# sweet_board_2020-08-14_14-36-53.net
KiCad netlist of a schematic drawn in EasyEDA
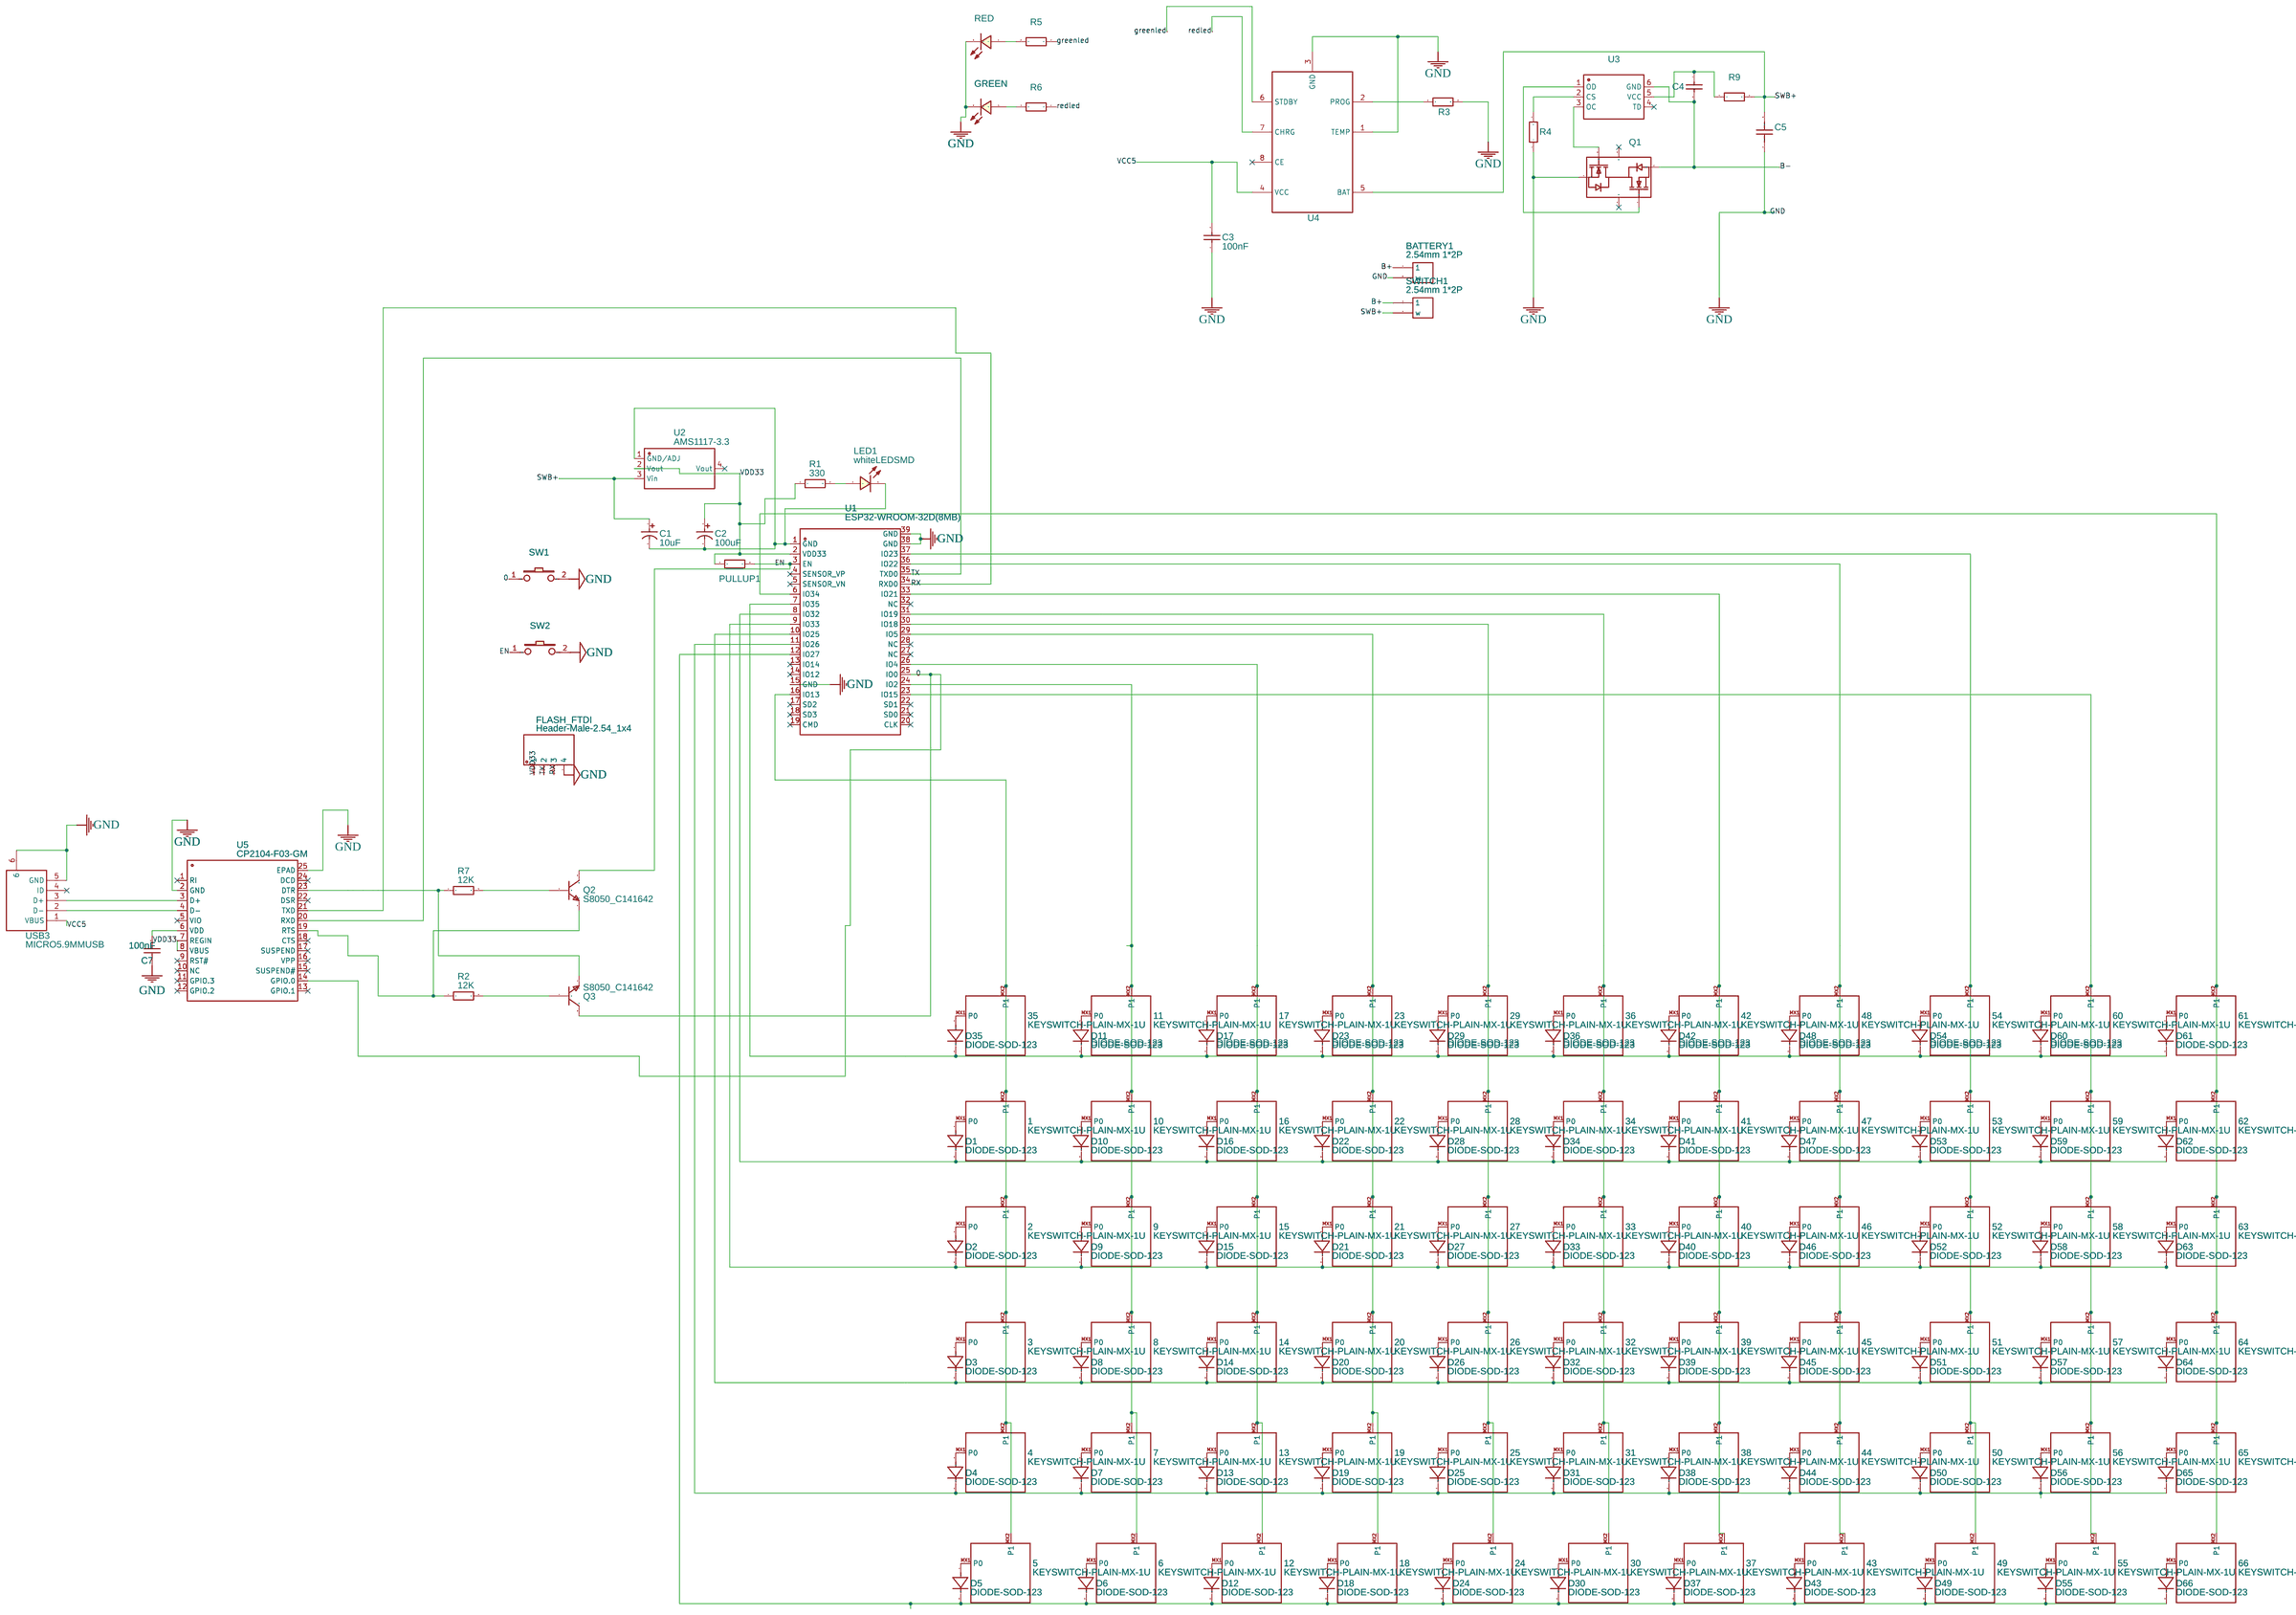
[diagram p0: Sheet_1]
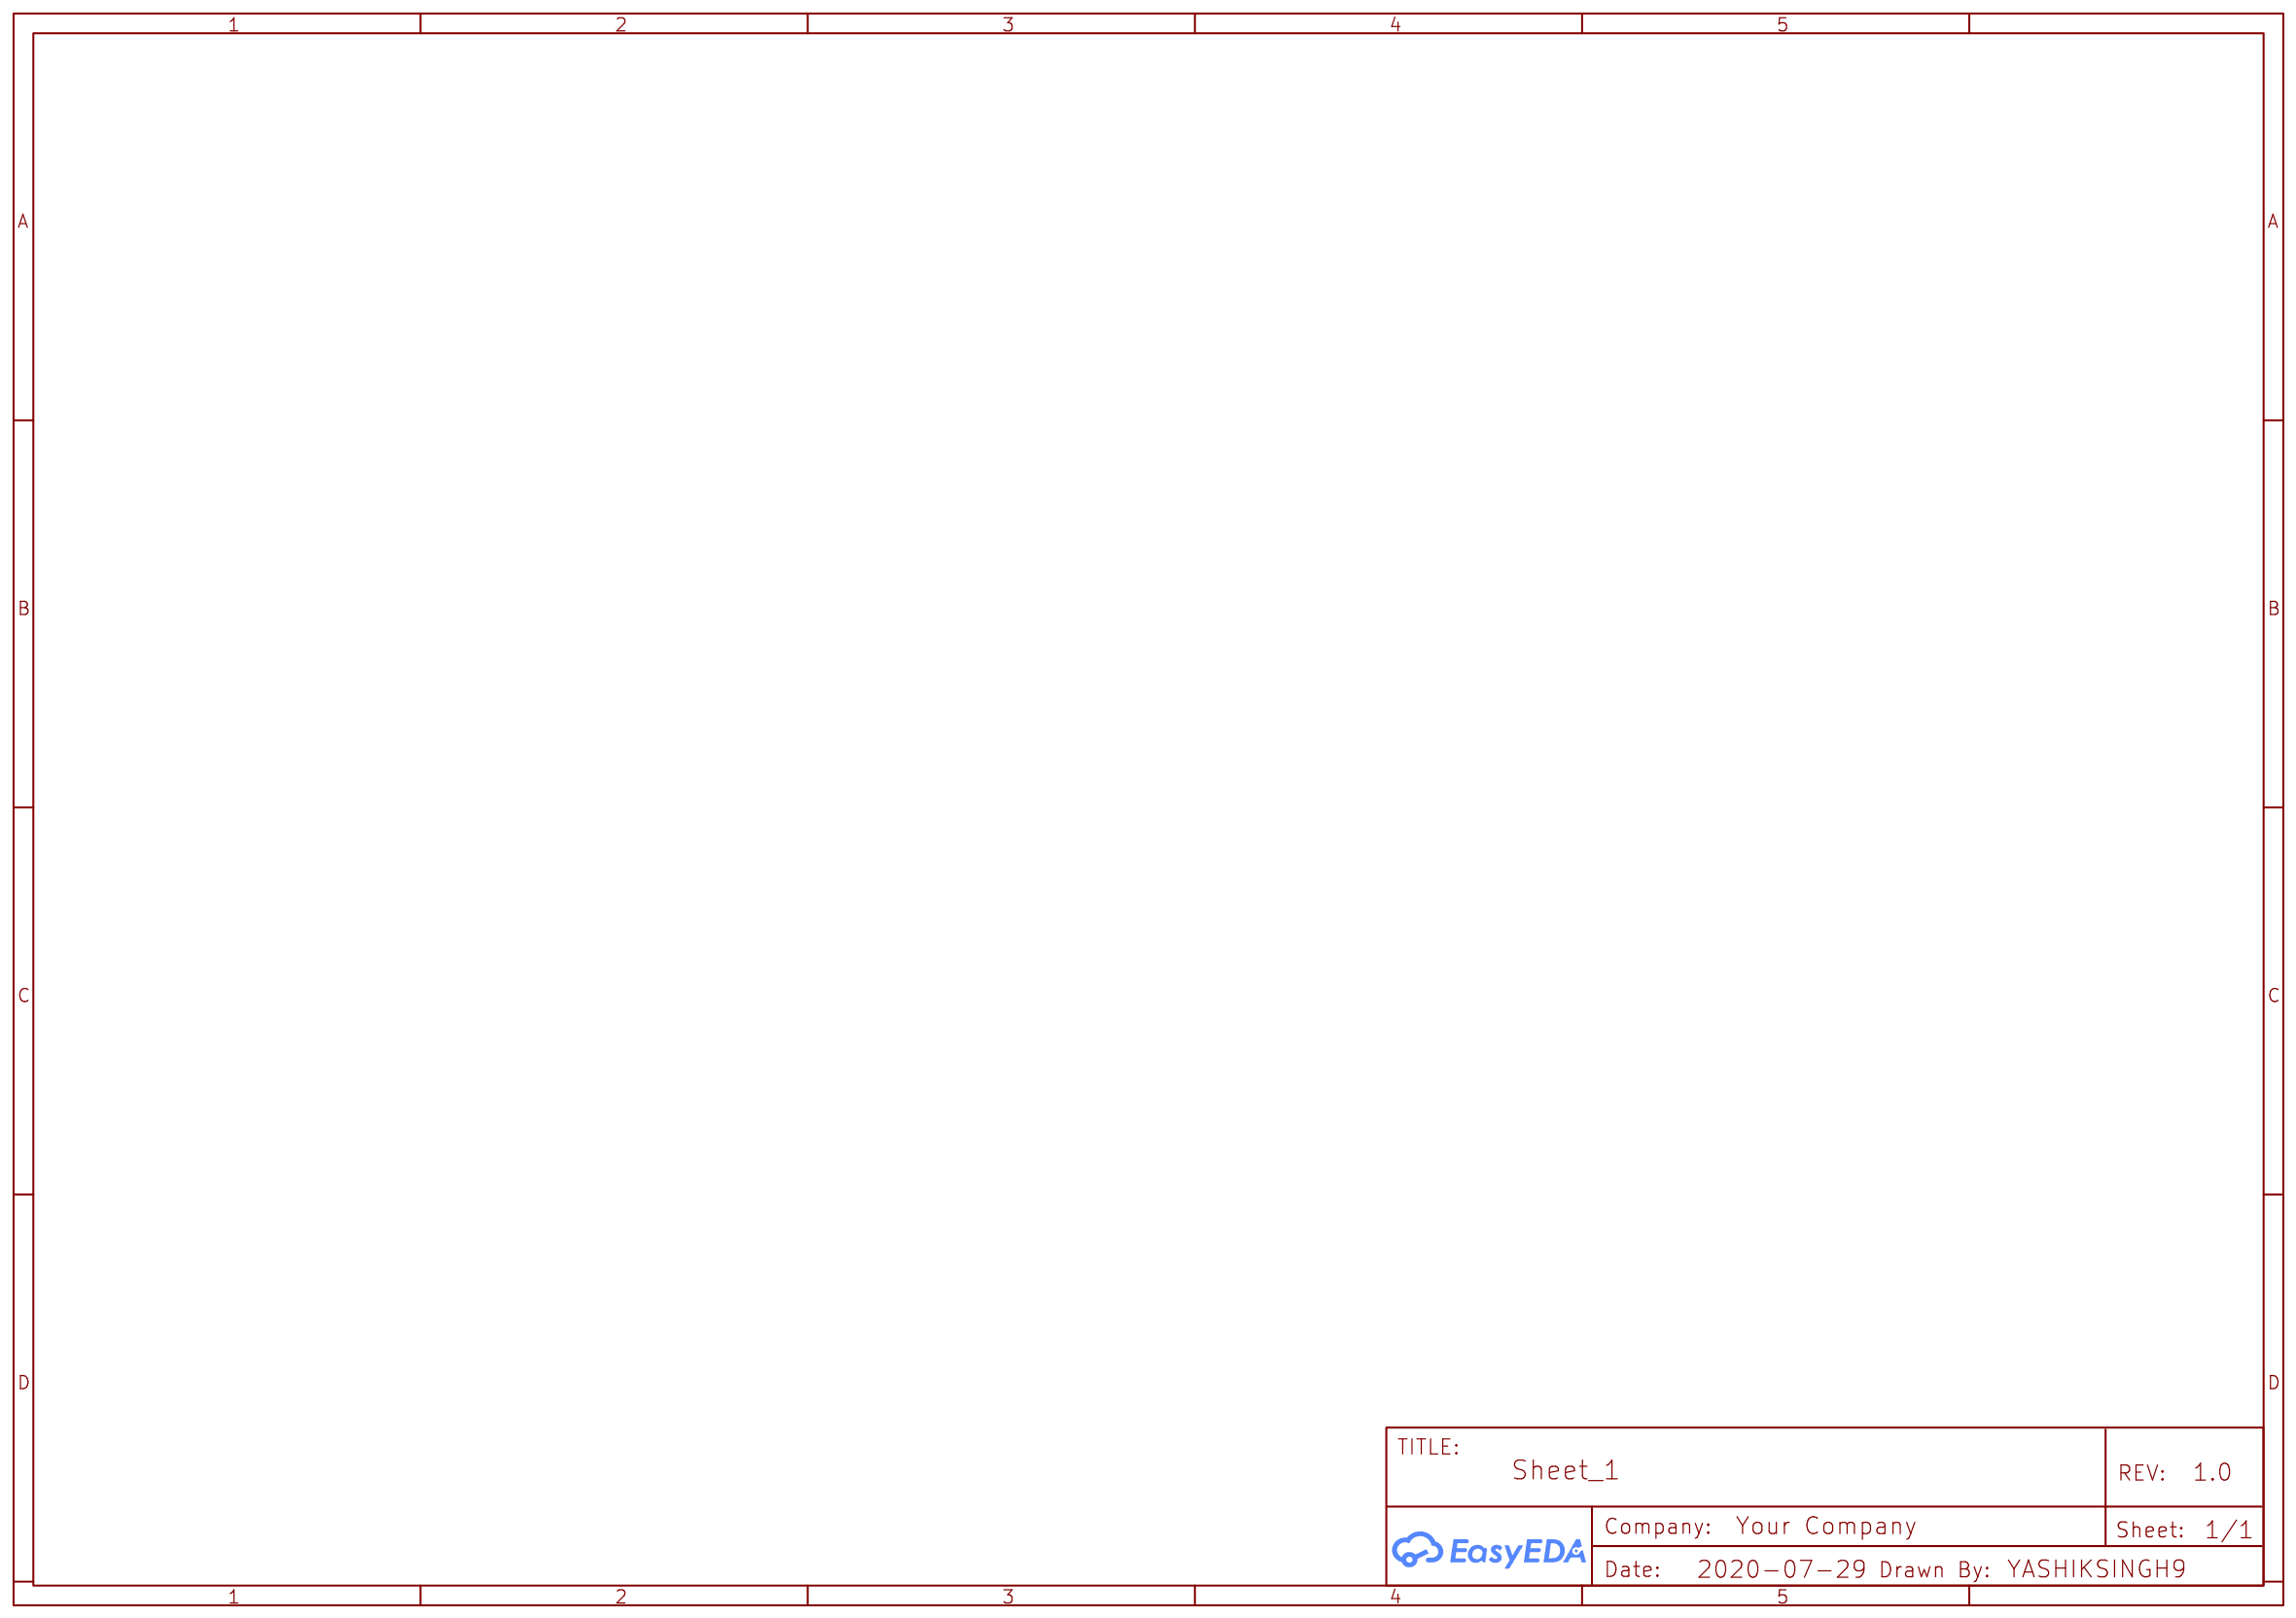
[diagram p1: over_under_charge]

(export (version "E")
  (design (tool "Eeschema 10.0.6"))
  (components
    (comp (ref "1") (value "KEYSWITCH-PLAIN-MX-1U") (libsource (lib "") (part "KEYSWITCH-PLAIN-MX-1U")))
    (comp (ref "2") (value "KEYSWITCH-PLAIN-MX-1U") (libsource (lib "") (part "KEYSWITCH-PLAIN-MX-1U")))
    (comp (ref "3") (value "KEYSWITCH-PLAIN-MX-1U") (libsource (lib "") (part "KEYSWITCH-PLAIN-MX-1U")))
    (comp (ref "4") (value "KEYSWITCH-PLAIN-MX-1U") (libsource (lib "") (part "KEYSWITCH-PLAIN-MX-1U")))
    (comp (ref "5") (value "KEYSWITCH-PLAIN-MX-1U") (libsource (lib "") (part "KEYSWITCH-PLAIN-MX-1U")))
    (comp (ref "6") (value "KEYSWITCH-PLAIN-MX-1U") (libsource (lib "") (part "KEYSWITCH-PLAIN-MX-1U")))
    (comp (ref "7") (value "KEYSWITCH-PLAIN-MX-1U") (libsource (lib "") (part "KEYSWITCH-PLAIN-MX-1U")))
    (comp (ref "8") (value "KEYSWITCH-PLAIN-MX-1U") (libsource (lib "") (part "KEYSWITCH-PLAIN-MX-1U")))
    (comp (ref "9") (value "KEYSWITCH-PLAIN-MX-1U") (libsource (lib "") (part "KEYSWITCH-PLAIN-MX-1U")))
    (comp (ref "10") (value "KEYSWITCH-PLAIN-MX-1U") (libsource (lib "") (part "KEYSWITCH-PLAIN-MX-1U")))
    (comp (ref "11") (value "KEYSWITCH-PLAIN-MX-1U") (libsource (lib "") (part "KEYSWITCH-PLAIN-MX-1U")))
    (comp (ref "12") (value "KEYSWITCH-PLAIN-MX-1U") (libsource (lib "") (part "KEYSWITCH-PLAIN-MX-1U")))
    (comp (ref "13") (value "KEYSWITCH-PLAIN-MX-1U") (libsource (lib "") (part "KEYSWITCH-PLAIN-MX-1U")))
    (comp (ref "14") (value "KEYSWITCH-PLAIN-MX-1U") (libsource (lib "") (part "KEYSWITCH-PLAIN-MX-1U")))
    (comp (ref "15") (value "KEYSWITCH-PLAIN-MX-1U") (libsource (lib "") (part "KEYSWITCH-PLAIN-MX-1U")))
    (comp (ref "16") (value "KEYSWITCH-PLAIN-MX-1U") (libsource (lib "") (part "KEYSWITCH-PLAIN-MX-1U")))
    (comp (ref "17") (value "KEYSWITCH-PLAIN-MX-1U") (libsource (lib "") (part "KEYSWITCH-PLAIN-MX-1U")))
    (comp (ref "18") (value "KEYSWITCH-PLAIN-MX-1U") (libsource (lib "") (part "KEYSWITCH-PLAIN-MX-1U")))
    (comp (ref "19") (value "KEYSWITCH-PLAIN-MX-1U") (libsource (lib "") (part "KEYSWITCH-PLAIN-MX-1U")))
    (comp (ref "20") (value "KEYSWITCH-PLAIN-MX-1U") (libsource (lib "") (part "KEYSWITCH-PLAIN-MX-1U")))
    (comp (ref "21") (value "KEYSWITCH-PLAIN-MX-1U") (libsource (lib "") (part "KEYSWITCH-PLAIN-MX-1U")))
    (comp (ref "22") (value "KEYSWITCH-PLAIN-MX-1U") (libsource (lib "") (part "KEYSWITCH-PLAIN-MX-1U")))
    (comp (ref "23") (value "KEYSWITCH-PLAIN-MX-1U") (libsource (lib "") (part "KEYSWITCH-PLAIN-MX-1U")))
    (comp (ref "24") (value "KEYSWITCH-PLAIN-MX-1U") (libsource (lib "") (part "KEYSWITCH-PLAIN-MX-1U")))
    (comp (ref "25") (value "KEYSWITCH-PLAIN-MX-1U") (libsource (lib "") (part "KEYSWITCH-PLAIN-MX-1U")))
    (comp (ref "26") (value "KEYSWITCH-PLAIN-MX-1U") (libsource (lib "") (part "KEYSWITCH-PLAIN-MX-1U")))
    (comp (ref "27") (value "KEYSWITCH-PLAIN-MX-1U") (libsource (lib "") (part "KEYSWITCH-PLAIN-MX-1U")))
    (comp (ref "28") (value "KEYSWITCH-PLAIN-MX-1U") (libsource (lib "") (part "KEYSWITCH-PLAIN-MX-1U")))
    (comp (ref "29") (value "KEYSWITCH-PLAIN-MX-1U") (libsource (lib "") (part "KEYSWITCH-PLAIN-MX-1U")))
    (comp (ref "30") (value "KEYSWITCH-PLAIN-MX-1U") (libsource (lib "") (part "KEYSWITCH-PLAIN-MX-1U")))
    (comp (ref "31") (value "KEYSWITCH-PLAIN-MX-1U") (libsource (lib "") (part "KEYSWITCH-PLAIN-MX-1U")))
    (comp (ref "32") (value "KEYSWITCH-PLAIN-MX-1U") (libsource (lib "") (part "KEYSWITCH-PLAIN-MX-1U")))
    (comp (ref "33") (value "KEYSWITCH-PLAIN-MX-1U") (libsource (lib "") (part "KEYSWITCH-PLAIN-MX-1U")))
    (comp (ref "34") (value "KEYSWITCH-PLAIN-MX-1U") (libsource (lib "") (part "KEYSWITCH-PLAIN-MX-1U")))
    (comp (ref "35") (value "KEYSWITCH-PLAIN-MX-1U") (libsource (lib "") (part "KEYSWITCH-PLAIN-MX-1U")))
    (comp (ref "36") (value "KEYSWITCH-PLAIN-MX-1U") (libsource (lib "") (part "KEYSWITCH-PLAIN-MX-1U")))
    (comp (ref "37") (value "KEYSWITCH-PLAIN-MX-1U") (libsource (lib "") (part "KEYSWITCH-PLAIN-MX-1U")))
    (comp (ref "38") (value "KEYSWITCH-PLAIN-MX-1U") (libsource (lib "") (part "KEYSWITCH-PLAIN-MX-1U")))
    (comp (ref "39") (value "KEYSWITCH-PLAIN-MX-1U") (libsource (lib "") (part "KEYSWITCH-PLAIN-MX-1U")))
    (comp (ref "40") (value "KEYSWITCH-PLAIN-MX-1U") (libsource (lib "") (part "KEYSWITCH-PLAIN-MX-1U")))
    (comp (ref "41") (value "KEYSWITCH-PLAIN-MX-1U") (libsource (lib "") (part "KEYSWITCH-PLAIN-MX-1U")))
    (comp (ref "42") (value "KEYSWITCH-PLAIN-MX-1U") (libsource (lib "") (part "KEYSWITCH-PLAIN-MX-1U")))
    (comp (ref "43") (value "KEYSWITCH-PLAIN-MX-1U") (libsource (lib "") (part "KEYSWITCH-PLAIN-MX-1U")))
    (comp (ref "44") (value "KEYSWITCH-PLAIN-MX-1U") (libsource (lib "") (part "KEYSWITCH-PLAIN-MX-1U")))
    (comp (ref "45") (value "KEYSWITCH-PLAIN-MX-1U") (libsource (lib "") (part "KEYSWITCH-PLAIN-MX-1U")))
    (comp (ref "46") (value "KEYSWITCH-PLAIN-MX-1U") (libsource (lib "") (part "KEYSWITCH-PLAIN-MX-1U")))
    (comp (ref "47") (value "KEYSWITCH-PLAIN-MX-1U") (libsource (lib "") (part "KEYSWITCH-PLAIN-MX-1U")))
    (comp (ref "48") (value "KEYSWITCH-PLAIN-MX-1U") (libsource (lib "") (part "KEYSWITCH-PLAIN-MX-1U")))
    (comp (ref "49") (value "KEYSWITCH-PLAIN-MX-1U") (libsource (lib "") (part "KEYSWITCH-PLAIN-MX-1U")))
    (comp (ref "50") (value "KEYSWITCH-PLAIN-MX-1U") (libsource (lib "") (part "KEYSWITCH-PLAIN-MX-1U")))
    (comp (ref "51") (value "KEYSWITCH-PLAIN-MX-1U") (libsource (lib "") (part "KEYSWITCH-PLAIN-MX-1U")))
    (comp (ref "52") (value "KEYSWITCH-PLAIN-MX-1U") (libsource (lib "") (part "KEYSWITCH-PLAIN-MX-1U")))
    (comp (ref "53") (value "KEYSWITCH-PLAIN-MX-1U") (libsource (lib "") (part "KEYSWITCH-PLAIN-MX-1U")))
    (comp (ref "54") (value "KEYSWITCH-PLAIN-MX-1U") (libsource (lib "") (part "KEYSWITCH-PLAIN-MX-1U")))
    (comp (ref "55") (value "KEYSWITCH-PLAIN-MX-1U") (libsource (lib "") (part "KEYSWITCH-PLAIN-MX-1U")))
    (comp (ref "56") (value "KEYSWITCH-PLAIN-MX-1U") (libsource (lib "") (part "KEYSWITCH-PLAIN-MX-1U")))
    (comp (ref "57") (value "KEYSWITCH-PLAIN-MX-1U") (libsource (lib "") (part "KEYSWITCH-PLAIN-MX-1U")))
    (comp (ref "58") (value "KEYSWITCH-PLAIN-MX-1U") (libsource (lib "") (part "KEYSWITCH-PLAIN-MX-1U")))
    (comp (ref "59") (value "KEYSWITCH-PLAIN-MX-1U") (libsource (lib "") (part "KEYSWITCH-PLAIN-MX-1U")))
    (comp (ref "60") (value "KEYSWITCH-PLAIN-MX-1U") (libsource (lib "") (part "KEYSWITCH-PLAIN-MX-1U")))
    (comp (ref "61") (value "KEYSWITCH-PLAIN-MX-1U") (libsource (lib "") (part "KEYSWITCH-PLAIN-MX-1U")))
    (comp (ref "62") (value "KEYSWITCH-PLAIN-MX-1U") (libsource (lib "") (part "KEYSWITCH-PLAIN-MX-1U")))
    (comp (ref "63") (value "KEYSWITCH-PLAIN-MX-1U") (libsource (lib "") (part "KEYSWITCH-PLAIN-MX-1U")))
    (comp (ref "64") (value "KEYSWITCH-PLAIN-MX-1U") (libsource (lib "") (part "KEYSWITCH-PLAIN-MX-1U")))
    (comp (ref "65") (value "KEYSWITCH-PLAIN-MX-1U") (libsource (lib "") (part "KEYSWITCH-PLAIN-MX-1U")))
    (comp (ref "66") (value "KEYSWITCH-PLAIN-MX-1U") (libsource (lib "") (part "KEYSWITCH-PLAIN-MX-1U")))
    (comp (ref "BATTERY1")
      (value "2.54mm 1*2P")
      (fields (field (name "BOM_Supplier Part") "C36717"))
      (libsource (lib "") (part "2.54mm 1*2P"))
    )
    (comp (ref "C1")
      (value "10uF")
      (fields
        (field (name "BOM_Manufacturer Part") "10uF 25V 5*11")
        (field (name "BOM_Supplier Part") "C43347")
      )
      (libsource (lib "") (part "10uF 25V 5*11"))
    )
    (comp (ref "C2")
      (value "100uF")
      (fields
        (field (name "BOM_Manufacturer Part") "100uF 25V 5*11")
        (field (name "BOM_Supplier Part") "C47873")
      )
      (libsource (lib "") (part "100uF 25V 5*11"))
    )
    (comp (ref "C3")
      (value "100nF")
      (fields
        (field (name "BOM_Manufacturer Part") "0603B104K250")
        (field (name "BOM_Supplier Part") "C83054")
      )
      (libsource (lib "") (part "0603B104K250"))
    )
    (comp (ref "C4")
      (value "100nF")
      (fields
        (field (name "BOM_Manufacturer Part") "0603B104K250")
        (field (name "BOM_Supplier Part") "C83054")
      )
      (libsource (lib "") (part "0603B104K250_1"))
    )
    (comp (ref "C5")
      (value "10uF")
      (fields
        (field (name "BOM_Manufacturer Part") "CL10A106MP8NNNC")
        (field (name "BOM_Supplier Part") "C85713")
      )
      (libsource (lib "") (part "CL10A106MP8NNNC"))
    )
    (comp (ref "C7")
      (value "100nF")
      (fields
        (field (name "BOM_Manufacturer Part") "Calibration capacitor100nF（104）100V,5%")
        (field (name "BOM_Supplier Part") "C26609")
      )
      (libsource (lib "") (part "Calibration capacitor100nF（104）100V,5%"))
    )
    (comp (ref "D1") (value "DIODE-SOD-123") (libsource (lib "") (part "DIODE-SOD-123")))
    (comp (ref "D2") (value "DIODE-SOD-123") (libsource (lib "") (part "DIODE-SOD-123")))
    (comp (ref "D3") (value "DIODE-SOD-123") (libsource (lib "") (part "DIODE-SOD-123")))
    (comp (ref "D4") (value "DIODE-SOD-123") (libsource (lib "") (part "DIODE-SOD-123")))
    (comp (ref "D5") (value "DIODE-SOD-123") (libsource (lib "") (part "DIODE-SOD-123")))
    (comp (ref "D6") (value "DIODE-SOD-123") (libsource (lib "") (part "DIODE-SOD-123")))
    (comp (ref "D7") (value "DIODE-SOD-123") (libsource (lib "") (part "DIODE-SOD-123")))
    (comp (ref "D8") (value "DIODE-SOD-123") (libsource (lib "") (part "DIODE-SOD-123")))
    (comp (ref "D9") (value "DIODE-SOD-123") (libsource (lib "") (part "DIODE-SOD-123")))
    (comp (ref "D10") (value "DIODE-SOD-123") (libsource (lib "") (part "DIODE-SOD-123")))
    (comp (ref "D11") (value "DIODE-SOD-123") (libsource (lib "") (part "DIODE-SOD-123")))
    (comp (ref "D12") (value "DIODE-SOD-123") (libsource (lib "") (part "DIODE-SOD-123")))
    (comp (ref "D13") (value "DIODE-SOD-123") (libsource (lib "") (part "DIODE-SOD-123")))
    (comp (ref "D14") (value "DIODE-SOD-123") (libsource (lib "") (part "DIODE-SOD-123")))
    (comp (ref "D15") (value "DIODE-SOD-123") (libsource (lib "") (part "DIODE-SOD-123")))
    (comp (ref "D16") (value "DIODE-SOD-123") (libsource (lib "") (part "DIODE-SOD-123")))
    (comp (ref "D17") (value "DIODE-SOD-123") (libsource (lib "") (part "DIODE-SOD-123")))
    (comp (ref "D18") (value "DIODE-SOD-123") (libsource (lib "") (part "DIODE-SOD-123")))
    (comp (ref "D19") (value "DIODE-SOD-123") (libsource (lib "") (part "DIODE-SOD-123")))
    (comp (ref "D20") (value "DIODE-SOD-123") (libsource (lib "") (part "DIODE-SOD-123")))
    (comp (ref "D21") (value "DIODE-SOD-123") (libsource (lib "") (part "DIODE-SOD-123")))
    (comp (ref "D22") (value "DIODE-SOD-123") (libsource (lib "") (part "DIODE-SOD-123")))
    (comp (ref "D23") (value "DIODE-SOD-123") (libsource (lib "") (part "DIODE-SOD-123")))
    (comp (ref "D24") (value "DIODE-SOD-123") (libsource (lib "") (part "DIODE-SOD-123")))
    (comp (ref "D25") (value "DIODE-SOD-123") (libsource (lib "") (part "DIODE-SOD-123")))
    (comp (ref "D26") (value "DIODE-SOD-123") (libsource (lib "") (part "DIODE-SOD-123")))
    (comp (ref "D27") (value "DIODE-SOD-123") (libsource (lib "") (part "DIODE-SOD-123")))
    (comp (ref "D28") (value "DIODE-SOD-123") (libsource (lib "") (part "DIODE-SOD-123")))
    (comp (ref "D29") (value "DIODE-SOD-123") (libsource (lib "") (part "DIODE-SOD-123")))
    (comp (ref "D30") (value "DIODE-SOD-123") (libsource (lib "") (part "DIODE-SOD-123")))
    (comp (ref "D31") (value "DIODE-SOD-123") (libsource (lib "") (part "DIODE-SOD-123")))
    (comp (ref "D32") (value "DIODE-SOD-123") (libsource (lib "") (part "DIODE-SOD-123")))
    (comp (ref "D33") (value "DIODE-SOD-123") (libsource (lib "") (part "DIODE-SOD-123")))
    (comp (ref "D34") (value "DIODE-SOD-123") (libsource (lib "") (part "DIODE-SOD-123")))
    (comp (ref "D35") (value "DIODE-SOD-123") (libsource (lib "") (part "DIODE-SOD-123")))
    (comp (ref "D36") (value "DIODE-SOD-123") (libsource (lib "") (part "DIODE-SOD-123")))
    (comp (ref "D37") (value "DIODE-SOD-123") (libsource (lib "") (part "DIODE-SOD-123")))
    (comp (ref "D38") (value "DIODE-SOD-123") (libsource (lib "") (part "DIODE-SOD-123")))
    (comp (ref "D39") (value "DIODE-SOD-123") (libsource (lib "") (part "DIODE-SOD-123")))
    (comp (ref "D40") (value "DIODE-SOD-123") (libsource (lib "") (part "DIODE-SOD-123")))
    (comp (ref "D41") (value "DIODE-SOD-123") (libsource (lib "") (part "DIODE-SOD-123")))
    (comp (ref "D42") (value "DIODE-SOD-123") (libsource (lib "") (part "DIODE-SOD-123")))
    (comp (ref "D43") (value "DIODE-SOD-123") (libsource (lib "") (part "DIODE-SOD-123")))
    (comp (ref "D44") (value "DIODE-SOD-123") (libsource (lib "") (part "DIODE-SOD-123")))
    (comp (ref "D45") (value "DIODE-SOD-123") (libsource (lib "") (part "DIODE-SOD-123")))
    (comp (ref "D46") (value "DIODE-SOD-123") (libsource (lib "") (part "DIODE-SOD-123")))
    (comp (ref "D47") (value "DIODE-SOD-123") (libsource (lib "") (part "DIODE-SOD-123")))
    (comp (ref "D48") (value "DIODE-SOD-123") (libsource (lib "") (part "DIODE-SOD-123")))
    (comp (ref "D49") (value "DIODE-SOD-123") (libsource (lib "") (part "DIODE-SOD-123")))
    (comp (ref "D50") (value "DIODE-SOD-123") (libsource (lib "") (part "DIODE-SOD-123")))
    (comp (ref "D51") (value "DIODE-SOD-123") (libsource (lib "") (part "DIODE-SOD-123")))
    (comp (ref "D52") (value "DIODE-SOD-123") (libsource (lib "") (part "DIODE-SOD-123")))
    (comp (ref "D53") (value "DIODE-SOD-123") (libsource (lib "") (part "DIODE-SOD-123")))
    (comp (ref "D54") (value "DIODE-SOD-123") (libsource (lib "") (part "DIODE-SOD-123")))
    (comp (ref "D55") (value "DIODE-SOD-123") (libsource (lib "") (part "DIODE-SOD-123")))
    (comp (ref "D56") (value "DIODE-SOD-123") (libsource (lib "") (part "DIODE-SOD-123")))
    (comp (ref "D57") (value "DIODE-SOD-123") (libsource (lib "") (part "DIODE-SOD-123")))
    (comp (ref "D58") (value "DIODE-SOD-123") (libsource (lib "") (part "DIODE-SOD-123")))
    (comp (ref "D59") (value "DIODE-SOD-123") (libsource (lib "") (part "DIODE-SOD-123")))
    (comp (ref "D60") (value "DIODE-SOD-123") (libsource (lib "") (part "DIODE-SOD-123")))
    (comp (ref "D61") (value "DIODE-SOD-123") (libsource (lib "") (part "DIODE-SOD-123")))
    (comp (ref "D62") (value "DIODE-SOD-123") (libsource (lib "") (part "DIODE-SOD-123")))
    (comp (ref "D63") (value "DIODE-SOD-123") (libsource (lib "") (part "DIODE-SOD-123")))
    (comp (ref "D64") (value "DIODE-SOD-123") (libsource (lib "") (part "DIODE-SOD-123")))
    (comp (ref "D65") (value "DIODE-SOD-123") (libsource (lib "") (part "DIODE-SOD-123")))
    (comp (ref "D66") (value "DIODE-SOD-123") (libsource (lib "") (part "DIODE-SOD-123")))
    (comp (ref "FLASH_FTDI")
      (value "Header-Male-2.54_1x4")
      (fields
        (field (name "BOM_Manufacturer Part") "210S-1*4P L=11.6MMGold-plated black")
        (field (name "BOM_Supplier Part") "C124378")
      )
      (libsource (lib "") (part "Unknown_-95_-125"))
    )
    (comp (ref "GREEN")
      (value "green")
      (fields
        (field (name "BOM_Manufacturer Part") "whiteLEDSMD")
        (field (name "BOM_Supplier Part") "C34499")
      )
      (libsource (lib "") (part "whiteLEDSMD_2"))
    )
    (comp (ref "LED1")
      (value "whiteLEDSMD")
      (fields (field (name "BOM_Supplier Part") "C34499"))
      (libsource (lib "") (part "whiteLEDSMD"))
    )
    (comp (ref "PULLUP1")
      (value "10k")
      (fields
        (field (name "BOM_Manufacturer Part") "RS-03K000JT")
        (field (name "BOM_Supplier Part") "C115304")
      )
      (libsource (lib "") (part "RS-03K000JT"))
    )
    (comp (ref "Q1")
      (value "FS8205")
      (fields (field (name "BOM_Supplier Part") "C32254"))
      (libsource (lib "") (part "Unknown_970_-700"))
    )
    (comp (ref "Q2")
      (value "S8050_C141642")
      (fields (field (name "BOM_Manufacturer Part") "S8050") (field (name "BOM_Supplier Part") "C141642"))
      (libsource (lib "") (part "S8050_C141642_1"))
    )
    (comp (ref "Q3")
      (value "S8050_C141642")
      (fields (field (name "BOM_Manufacturer Part") "S8050") (field (name "BOM_Supplier Part") "C141642"))
      (libsource (lib "") (part "S8050_C141642"))
    )
    (comp (ref "R1")
      (value "330")
      (fields (field (name "BOM_Supplier Part") "C10322"))
      (libsource (lib "") (part "330Ω (331) ±5%"))
    )
    (comp (ref "R2")
      (value "12K")
      (fields
        (field (name "BOM_Manufacturer Part") "RN1/2W12KΩFT/BA1")
        (field (name "BOM_Supplier Part") "C385571")
      )
      (libsource (lib "") (part "RN1/2W12KΩFT/BA1"))
    )
    (comp (ref "R3")
      (value "1.2KΩ")
      (fields
        (field (name "BOM_Manufacturer Part") "RC0603JR-071K2L")
        (field (name "BOM_Supplier Part") "C114679")
      )
      (libsource (lib "") (part "RC0603JR-071K2L"))
    )
    (comp (ref "R4")
      (value "1K")
      (fields
        (field (name "BOM_Manufacturer Part") "ERJ3GEYJ102V")
        (field (name "BOM_Supplier Part") "C180848")
      )
      (libsource (lib "") (part "ERJ3GEYJ102V"))
    )
    (comp (ref "R5")
      (value "220")
      (fields
        (field (name "BOM_Manufacturer Part") "RS-03K000JT")
        (field (name "BOM_Supplier Part") "C115304")
      )
      (libsource (lib "") (part "RS-03K000JT_1"))
    )
    (comp (ref "R6")
      (value "220")
      (fields
        (field (name "BOM_Manufacturer Part") "RS-03K000JT")
        (field (name "BOM_Supplier Part") "C115304")
      )
      (libsource (lib "") (part "RS-03K000JT_1"))
    )
    (comp (ref "R7")
      (value "12K")
      (fields
        (field (name "BOM_Manufacturer Part") "RN1/2W12KΩFT/BA1")
        (field (name "BOM_Supplier Part") "C385571")
      )
      (libsource (lib "") (part "RN1/2W12KΩFT/BA1"))
    )
    (comp (ref "R9")
      (value "100Ω")
      (fields
        (field (name "BOM_Manufacturer Part") "0603WAJ0101T5E")
        (field (name "BOM_Supplier Part") "C25201")
      )
      (libsource (lib "") (part "0603WAJ0101T5E"))
    )
    (comp (ref "RED")
      (value "red")
      (fields
        (field (name "BOM_Manufacturer Part") "whiteLEDSMD")
        (field (name "BOM_Supplier Part") "C34499")
      )
      (libsource (lib "") (part "whiteLEDSMD_1"))
    )
    (comp (ref "SW1")
      (value "3*6*2.5_SMD_Tactile_Switch")
      (fields
        (field (name "BOM_Manufacturer Part") "6*6*12SMD Tactile Switch")
        (field (name "BOM_Supplier Part") "C66637")
      )
      (libsource (lib "") (part "3*6*2.5_SMD_Tactile_Switch"))
    )
    (comp (ref "SW2")
      (value "3*6*2.5_SMD_Tactile_Switch")
      (fields
        (field (name "BOM_Manufacturer Part") "6*6*12SMD Tactile Switch")
        (field (name "BOM_Supplier Part") "C66637")
      )
      (libsource (lib "") (part "3*6*2.5_SMD_Tactile_Switch"))
    )
    (comp (ref "SWITCH1")
      (value "2.54mm 1*2P")
      (fields (field (name "BOM_Supplier Part") "C36717"))
      (libsource (lib "") (part "2.54mm 1*2P_1"))
    )
    (comp (ref "U1")
      (value "ESP32-WROOM-32D(8MB)")
      (fields (field (name "BOM_Supplier Part") "C529577"))
      (libsource (lib "") (part "ESP32-WROOM-32D(8MB)"))
    )
    (comp (ref "U2")
      (value "AMS1117-3.3")
      (fields (field (name "BOM_Supplier Part") "C6186"))
      (libsource (lib "") (part "AMS1117-3.3"))
    )
    (comp (ref "U3")
      (value "DW01A")
      (fields (field (name "BOM_Supplier Part") "C351410"))
      (libsource (lib "") (part "Unknown_965_-780"))
    )
    (comp (ref "U4")
      (value "TP4056")
      (fields (field (name "BOM_Supplier Part") "C16581"))
      (libsource (lib "") (part "Unknown_665_-745"))
    )
    (comp (ref "U5")
      (value "CP2104-F03-GM")
      (fields (field (name "BOM_Supplier Part") "C47742"))
      (libsource (lib "") (part "CP2104-F03-GM"))
    )
    (comp (ref "USB3")
      (value "MICRO5.9MMUSB")
      (fields
        (field (name "BOM_Manufacturer Part") "MICRO5.9mmusb")
        (field (name "BOM_Supplier Part") "C393940")
      )
      (libsource (lib "") (part "MICRO5.9MMUSB"))
    )
  )
  (nets
    (net (code "1") (name "0") (class "Default")
      (node (ref "Q3") (pin "3") (pinfunction "C_3") (pintype "unspecified"))
      (node (ref "SW1") (pin "1") (pinfunction "1_1") (pintype "input"))
      (node (ref "U1") (pin "25") (pinfunction "IO0_25") (pintype "unspecified"))
      (node (ref "U5") (pin "14") (pinfunction "GPIO.0_14") (pintype "unspecified"))
    )
    (net (code "2") (name "B+") (class "Default")
      (node (ref "BATTERY1") (pin "1") (pinfunction "1_1") (pintype "input"))
      (node (ref "SWITCH1") (pin "1") (pinfunction "1_1") (pintype "input"))
    )
    (net (code "3") (name "B-") (class "Default")
      (node (ref "C4") (pin "2") (pinfunction "2_2") (pintype "input"))
      (node (ref "Q1") (pin "3") (pinfunction "S2_3") (pintype "unspecified"))
      (node (ref "U3") (pin "6") (pinfunction "GND_6") (pintype "unspecified"))
    )
    (net (code "4") (name "EN") (class "Default")
      (node (ref "PULLUP1") (pin "2") (pinfunction "2_2") (pintype "input"))
      (node (ref "Q2") (pin "3") (pinfunction "C_3") (pintype "unspecified"))
      (node (ref "SW2") (pin "1") (pinfunction "1_1") (pintype "input"))
      (node (ref "U1") (pin "3") (pinfunction "EN_3") (pintype "unspecified"))
    )
    (net (code "5") (name "GND") (class "Default")
      (node (ref "BATTERY1") (pin "2") (pinfunction "w_2") (pintype "input"))
      (node (ref "C3") (pin "1") (pinfunction "1_1") (pintype "input"))
      (node (ref "C5") (pin "1") (pinfunction "1_1") (pintype "unspecified"))
      (node (ref "C7") (pin "1") (pinfunction "1_1") (pintype "input"))
      (node (ref "FLASH_FTDI") (pin "4") (pinfunction "4_4") (pintype "unspecified"))
      (node (ref "GREEN") (pin "2") (pinfunction "K_2") (pintype "unspecified"))
      (node (ref "Q1") (pin "1") (pinfunction "S1_1") (pintype "unspecified"))
      (node (ref "R3") (pin "2") (pinfunction "2_2") (pintype "input"))
      (node (ref "R4") (pin "1") (pinfunction "1_1") (pintype "unspecified"))
      (node (ref "RED") (pin "2") (pinfunction "K_2") (pintype "unspecified"))
      (node (ref "SW1") (pin "2") (pinfunction "2_2") (pintype "input"))
      (node (ref "SW2") (pin "2") (pinfunction "2_2") (pintype "input"))
      (node (ref "U1") (pin "15") (pinfunction "GND_15") (pintype "unspecified"))
      (node (ref "U1") (pin "38") (pinfunction "GND_38") (pintype "unspecified"))
      (node (ref "U1") (pin "39") (pinfunction "GND_39") (pintype "unspecified"))
      (node (ref "U4") (pin "1") (pinfunction "TEMP_1") (pintype "unspecified"))
      (node (ref "U4") (pin "3") (pinfunction "GND_3") (pintype "unspecified"))
      (node (ref "U5") (pin "2") (pinfunction "GND_2") (pintype "unspecified"))
      (node (ref "U5") (pin "25") (pinfunction "EPAD_25") (pintype "unspecified"))
      (node (ref "USB3") (pin "5") (pinfunction "GND_5") (pintype "unspecified"))
      (node (ref "USB3") (pin "6") (pinfunction "6_6") (pintype "unspecified"))
    )
    (net (code "6") (name "Net-(1-P0)") (class "Default")
      (node (ref "1") (pin "MX1") (pinfunction "P0_MX1") (pintype "bidirectional"))
      (node (ref "D1") (pin "A") (pinfunction "A_A") (pintype "bidirectional"))
    )
    (net (code "7") (name "Net-(1-P1)") (class "Default")
      (node (ref "1") (pin "MX2") (pinfunction "P1_MX2") (pintype "bidirectional"))
      (node (ref "2") (pin "MX2") (pinfunction "P1_MX2") (pintype "bidirectional"))
      (node (ref "3") (pin "MX2") (pinfunction "P1_MX2") (pintype "bidirectional"))
      (node (ref "35") (pin "MX2") (pinfunction "P1_MX2") (pintype "bidirectional"))
      (node (ref "4") (pin "MX2") (pinfunction "P1_MX2") (pintype "bidirectional"))
      (node (ref "5") (pin "MX2") (pinfunction "P1_MX2") (pintype "bidirectional"))
      (node (ref "U1") (pin "16") (pinfunction "IO13_16") (pintype "unspecified"))
    )
    (net (code "8") (name "Net-(2-P0)") (class "Default")
      (node (ref "2") (pin "MX1") (pinfunction "P0_MX1") (pintype "bidirectional"))
      (node (ref "D2") (pin "A") (pinfunction "A_A") (pintype "bidirectional"))
    )
    (net (code "9") (name "Net-(3-P0)") (class "Default")
      (node (ref "3") (pin "MX1") (pinfunction "P0_MX1") (pintype "bidirectional"))
      (node (ref "D3") (pin "A") (pinfunction "A_A") (pintype "bidirectional"))
    )
    (net (code "10") (name "Net-(4-P0)") (class "Default")
      (node (ref "4") (pin "MX1") (pinfunction "P0_MX1") (pintype "bidirectional"))
      (node (ref "D4") (pin "A") (pinfunction "A_A") (pintype "bidirectional"))
    )
    (net (code "11") (name "Net-(5-P0)") (class "Default")
      (node (ref "5") (pin "MX1") (pinfunction "P0_MX1") (pintype "bidirectional"))
      (node (ref "D5") (pin "A") (pinfunction "A_A") (pintype "bidirectional"))
    )
    (net (code "12") (name "Net-(6-P0)") (class "Default")
      (node (ref "6") (pin "MX1") (pinfunction "P0_MX1") (pintype "bidirectional"))
      (node (ref "D6") (pin "A") (pinfunction "A_A") (pintype "bidirectional"))
    )
    (net (code "13") (name "Net-(7-P0)") (class "Default")
      (node (ref "7") (pin "MX1") (pinfunction "P0_MX1") (pintype "bidirectional"))
      (node (ref "D7") (pin "A") (pinfunction "A_A") (pintype "bidirectional"))
    )
    (net (code "14") (name "Net-(8-P0)") (class "Default")
      (node (ref "8") (pin "MX1") (pinfunction "P0_MX1") (pintype "bidirectional"))
      (node (ref "D8") (pin "A") (pinfunction "A_A") (pintype "bidirectional"))
    )
    (net (code "15") (name "Net-(9-P0)") (class "Default")
      (node (ref "9") (pin "MX1") (pinfunction "P0_MX1") (pintype "bidirectional"))
      (node (ref "D9") (pin "A") (pinfunction "A_A") (pintype "bidirectional"))
    )
    (net (code "16") (name "Net-(10-P0)") (class "Default")
      (node (ref "10") (pin "MX1") (pinfunction "P0_MX1") (pintype "bidirectional"))
      (node (ref "D10") (pin "A") (pinfunction "A_A") (pintype "bidirectional"))
    )
    (net (code "17") (name "Net-(10-P1)") (class "Default")
      (node (ref "10") (pin "MX2") (pinfunction "P1_MX2") (pintype "bidirectional"))
      (node (ref "11") (pin "MX2") (pinfunction "P1_MX2") (pintype "bidirectional"))
      (node (ref "6") (pin "MX2") (pinfunction "P1_MX2") (pintype "bidirectional"))
      (node (ref "7") (pin "MX2") (pinfunction "P1_MX2") (pintype "bidirectional"))
      (node (ref "8") (pin "MX2") (pinfunction "P1_MX2") (pintype "bidirectional"))
      (node (ref "9") (pin "MX2") (pinfunction "P1_MX2") (pintype "bidirectional"))
      (node (ref "U1") (pin "24") (pinfunction "IO2_24") (pintype "unspecified"))
    )
    (net (code "18") (name "Net-(11-P0)") (class "Default")
      (node (ref "11") (pin "MX1") (pinfunction "P0_MX1") (pintype "bidirectional"))
      (node (ref "D11") (pin "A") (pinfunction "A_A") (pintype "bidirectional"))
    )
    (net (code "19") (name "Net-(12-P0)") (class "Default")
      (node (ref "12") (pin "MX1") (pinfunction "P0_MX1") (pintype "bidirectional"))
      (node (ref "D12") (pin "A") (pinfunction "A_A") (pintype "bidirectional"))
    )
    (net (code "20") (name "Net-(12-P1)") (class "Default")
      (node (ref "12") (pin "MX2") (pinfunction "P1_MX2") (pintype "bidirectional"))
      (node (ref "13") (pin "MX2") (pinfunction "P1_MX2") (pintype "bidirectional"))
      (node (ref "14") (pin "MX2") (pinfunction "P1_MX2") (pintype "bidirectional"))
      (node (ref "15") (pin "MX2") (pinfunction "P1_MX2") (pintype "bidirectional"))
      (node (ref "16") (pin "MX2") (pinfunction "P1_MX2") (pintype "bidirectional"))
      (node (ref "17") (pin "MX2") (pinfunction "P1_MX2") (pintype "bidirectional"))
      (node (ref "U1") (pin "26") (pinfunction "IO4_26") (pintype "unspecified"))
    )
    (net (code "21") (name "Net-(13-P0)") (class "Default")
      (node (ref "13") (pin "MX1") (pinfunction "P0_MX1") (pintype "bidirectional"))
      (node (ref "D13") (pin "A") (pinfunction "A_A") (pintype "bidirectional"))
    )
    (net (code "22") (name "Net-(14-P0)") (class "Default")
      (node (ref "14") (pin "MX1") (pinfunction "P0_MX1") (pintype "bidirectional"))
      (node (ref "D14") (pin "A") (pinfunction "A_A") (pintype "bidirectional"))
    )
    (net (code "23") (name "Net-(15-P0)") (class "Default")
      (node (ref "15") (pin "MX1") (pinfunction "P0_MX1") (pintype "bidirectional"))
      (node (ref "D15") (pin "A") (pinfunction "A_A") (pintype "bidirectional"))
    )
    (net (code "24") (name "Net-(16-P0)") (class "Default")
      (node (ref "16") (pin "MX1") (pinfunction "P0_MX1") (pintype "bidirectional"))
      (node (ref "D16") (pin "A") (pinfunction "A_A") (pintype "bidirectional"))
    )
    (net (code "25") (name "Net-(17-P0)") (class "Default")
      (node (ref "17") (pin "MX1") (pinfunction "P0_MX1") (pintype "bidirectional"))
      (node (ref "D17") (pin "A") (pinfunction "A_A") (pintype "bidirectional"))
    )
    (net (code "26") (name "Net-(18-P0)") (class "Default")
      (node (ref "18") (pin "MX1") (pinfunction "P0_MX1") (pintype "bidirectional"))
      (node (ref "D18") (pin "A") (pinfunction "A_A") (pintype "bidirectional"))
    )
    (net (code "27") (name "Net-(18-P1)") (class "Default")
      (node (ref "18") (pin "MX2") (pinfunction "P1_MX2") (pintype "bidirectional"))
      (node (ref "19") (pin "MX2") (pinfunction "P1_MX2") (pintype "bidirectional"))
      (node (ref "20") (pin "MX2") (pinfunction "P1_MX2") (pintype "bidirectional"))
      (node (ref "21") (pin "MX2") (pinfunction "P1_MX2") (pintype "bidirectional"))
      (node (ref "22") (pin "MX2") (pinfunction "P1_MX2") (pintype "bidirectional"))
      (node (ref "23") (pin "MX2") (pinfunction "P1_MX2") (pintype "bidirectional"))
      (node (ref "U1") (pin "29") (pinfunction "IO5_29") (pintype "unspecified"))
    )
    (net (code "28") (name "Net-(19-P0)") (class "Default")
      (node (ref "19") (pin "MX1") (pinfunction "P0_MX1") (pintype "bidirectional"))
      (node (ref "D19") (pin "A") (pinfunction "A_A") (pintype "bidirectional"))
    )
    (net (code "29") (name "Net-(20-P0)") (class "Default")
      (node (ref "20") (pin "MX1") (pinfunction "P0_MX1") (pintype "bidirectional"))
      (node (ref "D20") (pin "A") (pinfunction "A_A") (pintype "bidirectional"))
    )
    (net (code "30") (name "Net-(21-P0)") (class "Default")
      (node (ref "21") (pin "MX1") (pinfunction "P0_MX1") (pintype "bidirectional"))
      (node (ref "D21") (pin "A") (pinfunction "A_A") (pintype "bidirectional"))
    )
    (net (code "31") (name "Net-(22-P0)") (class "Default")
      (node (ref "22") (pin "MX1") (pinfunction "P0_MX1") (pintype "bidirectional"))
      (node (ref "D22") (pin "A") (pinfunction "A_A") (pintype "bidirectional"))
    )
    (net (code "32") (name "Net-(23-P0)") (class "Default")
      (node (ref "23") (pin "MX1") (pinfunction "P0_MX1") (pintype "bidirectional"))
      (node (ref "D23") (pin "A") (pinfunction "A_A") (pintype "bidirectional"))
    )
    (net (code "33") (name "Net-(24-P0)") (class "Default")
      (node (ref "24") (pin "MX1") (pinfunction "P0_MX1") (pintype "bidirectional"))
      (node (ref "D24") (pin "A") (pinfunction "A_A") (pintype "bidirectional"))
    )
    (net (code "34") (name "Net-(24-P1)") (class "Default")
      (node (ref "24") (pin "MX2") (pinfunction "P1_MX2") (pintype "bidirectional"))
      (node (ref "25") (pin "MX2") (pinfunction "P1_MX2") (pintype "bidirectional"))
      (node (ref "26") (pin "MX2") (pinfunction "P1_MX2") (pintype "bidirectional"))
      (node (ref "27") (pin "MX2") (pinfunction "P1_MX2") (pintype "bidirectional"))
      (node (ref "28") (pin "MX2") (pinfunction "P1_MX2") (pintype "bidirectional"))
      (node (ref "29") (pin "MX2") (pinfunction "P1_MX2") (pintype "bidirectional"))
      (node (ref "U1") (pin "30") (pinfunction "IO18_30") (pintype "unspecified"))
    )
    (net (code "35") (name "Net-(25-P0)") (class "Default")
      (node (ref "25") (pin "MX1") (pinfunction "P0_MX1") (pintype "bidirectional"))
      (node (ref "D25") (pin "A") (pinfunction "A_A") (pintype "bidirectional"))
    )
    (net (code "36") (name "Net-(26-P0)") (class "Default")
      (node (ref "26") (pin "MX1") (pinfunction "P0_MX1") (pintype "bidirectional"))
      (node (ref "D26") (pin "A") (pinfunction "A_A") (pintype "bidirectional"))
    )
    (net (code "37") (name "Net-(27-P0)") (class "Default")
      (node (ref "27") (pin "MX1") (pinfunction "P0_MX1") (pintype "bidirectional"))
      (node (ref "D27") (pin "A") (pinfunction "A_A") (pintype "bidirectional"))
    )
    (net (code "38") (name "Net-(28-P0)") (class "Default")
      (node (ref "28") (pin "MX1") (pinfunction "P0_MX1") (pintype "bidirectional"))
      (node (ref "D28") (pin "A") (pinfunction "A_A") (pintype "bidirectional"))
    )
    (net (code "39") (name "Net-(29-P0)") (class "Default")
      (node (ref "29") (pin "MX1") (pinfunction "P0_MX1") (pintype "bidirectional"))
      (node (ref "D29") (pin "A") (pinfunction "A_A") (pintype "bidirectional"))
    )
    (net (code "40") (name "Net-(30-P0)") (class "Default")
      (node (ref "30") (pin "MX1") (pinfunction "P0_MX1") (pintype "bidirectional"))
      (node (ref "D30") (pin "A") (pinfunction "A_A") (pintype "bidirectional"))
    )
    (net (code "41") (name "Net-(30-P1)") (class "Default")
      (node (ref "30") (pin "MX2") (pinfunction "P1_MX2") (pintype "bidirectional"))
      (node (ref "31") (pin "MX2") (pinfunction "P1_MX2") (pintype "bidirectional"))
      (node (ref "32") (pin "MX2") (pinfunction "P1_MX2") (pintype "bidirectional"))
      (node (ref "33") (pin "MX2") (pinfunction "P1_MX2") (pintype "bidirectional"))
      (node (ref "34") (pin "MX2") (pinfunction "P1_MX2") (pintype "bidirectional"))
      (node (ref "36") (pin "MX2") (pinfunction "P1_MX2") (pintype "bidirectional"))
      (node (ref "U1") (pin "31") (pinfunction "IO19_31") (pintype "unspecified"))
    )
    (net (code "42") (name "Net-(31-P0)") (class "Default")
      (node (ref "31") (pin "MX1") (pinfunction "P0_MX1") (pintype "bidirectional"))
      (node (ref "D31") (pin "A") (pinfunction "A_A") (pintype "bidirectional"))
    )
    (net (code "43") (name "Net-(32-P0)") (class "Default")
      (node (ref "32") (pin "MX1") (pinfunction "P0_MX1") (pintype "bidirectional"))
      (node (ref "D32") (pin "A") (pinfunction "A_A") (pintype "bidirectional"))
    )
    (net (code "44") (name "Net-(33-P0)") (class "Default")
      (node (ref "33") (pin "MX1") (pinfunction "P0_MX1") (pintype "bidirectional"))
      (node (ref "D33") (pin "A") (pinfunction "A_A") (pintype "bidirectional"))
    )
    (net (code "45") (name "Net-(34-P0)") (class "Default")
      (node (ref "34") (pin "MX1") (pinfunction "P0_MX1") (pintype "bidirectional"))
      (node (ref "D34") (pin "A") (pinfunction "A_A") (pintype "bidirectional"))
    )
    (net (code "46") (name "Net-(35-P0)") (class "Default")
      (node (ref "35") (pin "MX1") (pinfunction "P0_MX1") (pintype "bidirectional"))
      (node (ref "D35") (pin "A") (pinfunction "A_A") (pintype "bidirectional"))
    )
    (net (code "47") (name "Net-(36-P0)") (class "Default")
      (node (ref "36") (pin "MX1") (pinfunction "P0_MX1") (pintype "bidirectional"))
      (node (ref "D36") (pin "A") (pinfunction "A_A") (pintype "bidirectional"))
    )
    (net (code "48") (name "Net-(37-P0)") (class "Default")
      (node (ref "37") (pin "MX1") (pinfunction "P0_MX1") (pintype "bidirectional"))
      (node (ref "D37") (pin "A") (pinfunction "A_A") (pintype "bidirectional"))
    )
    (net (code "49") (name "Net-(37-P1)") (class "Default")
      (node (ref "37") (pin "MX2") (pinfunction "P1_MX2") (pintype "bidirectional"))
      (node (ref "38") (pin "MX2") (pinfunction "P1_MX2") (pintype "bidirectional"))
      (node (ref "39") (pin "MX2") (pinfunction "P1_MX2") (pintype "bidirectional"))
      (node (ref "40") (pin "MX2") (pinfunction "P1_MX2") (pintype "bidirectional"))
      (node (ref "41") (pin "MX2") (pinfunction "P1_MX2") (pintype "bidirectional"))
      (node (ref "42") (pin "MX2") (pinfunction "P1_MX2") (pintype "bidirectional"))
      (node (ref "U1") (pin "33") (pinfunction "IO21_33") (pintype "unspecified"))
    )
    (net (code "50") (name "Net-(38-P0)") (class "Default")
      (node (ref "38") (pin "MX1") (pinfunction "P0_MX1") (pintype "bidirectional"))
      (node (ref "D38") (pin "A") (pinfunction "A_A") (pintype "bidirectional"))
    )
    (net (code "51") (name "Net-(39-P0)") (class "Default")
      (node (ref "39") (pin "MX1") (pinfunction "P0_MX1") (pintype "bidirectional"))
      (node (ref "D39") (pin "A") (pinfunction "A_A") (pintype "bidirectional"))
    )
    (net (code "52") (name "Net-(40-P0)") (class "Default")
      (node (ref "40") (pin "MX1") (pinfunction "P0_MX1") (pintype "bidirectional"))
      (node (ref "D40") (pin "A") (pinfunction "A_A") (pintype "bidirectional"))
    )
    (net (code "53") (name "Net-(41-P0)") (class "Default")
      (node (ref "41") (pin "MX1") (pinfunction "P0_MX1") (pintype "bidirectional"))
      (node (ref "D41") (pin "A") (pinfunction "A_A") (pintype "bidirectional"))
    )
    (net (code "54") (name "Net-(42-P0)") (class "Default")
      (node (ref "42") (pin "MX1") (pinfunction "P0_MX1") (pintype "bidirectional"))
      (node (ref "D42") (pin "A") (pinfunction "A_A") (pintype "bidirectional"))
    )
    (net (code "55") (name "Net-(43-P0)") (class "Default")
      (node (ref "43") (pin "MX1") (pinfunction "P0_MX1") (pintype "bidirectional"))
      (node (ref "D43") (pin "A") (pinfunction "A_A") (pintype "bidirectional"))
    )
    (net (code "56") (name "Net-(43-P1)") (class "Default")
      (node (ref "43") (pin "MX2") (pinfunction "P1_MX2") (pintype "bidirectional"))
      (node (ref "44") (pin "MX2") (pinfunction "P1_MX2") (pintype "bidirectional"))
      (node (ref "45") (pin "MX2") (pinfunction "P1_MX2") (pintype "bidirectional"))
      (node (ref "46") (pin "MX2") (pinfunction "P1_MX2") (pintype "bidirectional"))
      (node (ref "47") (pin "MX2") (pinfunction "P1_MX2") (pintype "bidirectional"))
      (node (ref "48") (pin "MX2") (pinfunction "P1_MX2") (pintype "bidirectional"))
      (node (ref "U1") (pin "36") (pinfunction "IO22_36") (pintype "unspecified"))
    )
    (net (code "57") (name "Net-(44-P0)") (class "Default")
      (node (ref "44") (pin "MX1") (pinfunction "P0_MX1") (pintype "bidirectional"))
      (node (ref "D44") (pin "A") (pinfunction "A_A") (pintype "bidirectional"))
    )
    (net (code "58") (name "Net-(45-P0)") (class "Default")
      (node (ref "45") (pin "MX1") (pinfunction "P0_MX1") (pintype "bidirectional"))
      (node (ref "D45") (pin "A") (pinfunction "A_A") (pintype "bidirectional"))
    )
    (net (code "59") (name "Net-(46-P0)") (class "Default")
      (node (ref "46") (pin "MX1") (pinfunction "P0_MX1") (pintype "bidirectional"))
      (node (ref "D46") (pin "A") (pinfunction "A_A") (pintype "bidirectional"))
    )
    (net (code "60") (name "Net-(47-P0)") (class "Default")
      (node (ref "47") (pin "MX1") (pinfunction "P0_MX1") (pintype "bidirectional"))
      (node (ref "D47") (pin "A") (pinfunction "A_A") (pintype "bidirectional"))
    )
    (net (code "61") (name "Net-(48-P0)") (class "Default")
      (node (ref "48") (pin "MX1") (pinfunction "P0_MX1") (pintype "bidirectional"))
      (node (ref "D48") (pin "A") (pinfunction "A_A") (pintype "bidirectional"))
    )
    (net (code "62") (name "Net-(49-P0)") (class "Default")
      (node (ref "49") (pin "MX1") (pinfunction "P0_MX1") (pintype "bidirectional"))
      (node (ref "D49") (pin "A") (pinfunction "A_A") (pintype "bidirectional"))
    )
    (net (code "63") (name "Net-(49-P1)") (class "Default")
      (node (ref "49") (pin "MX2") (pinfunction "P1_MX2") (pintype "bidirectional"))
      (node (ref "50") (pin "MX2") (pinfunction "P1_MX2") (pintype "bidirectional"))
      (node (ref "51") (pin "MX2") (pinfunction "P1_MX2") (pintype "bidirectional"))
      (node (ref "52") (pin "MX2") (pinfunction "P1_MX2") (pintype "bidirectional"))
      (node (ref "53") (pin "MX2") (pinfunction "P1_MX2") (pintype "bidirectional"))
      (node (ref "54") (pin "MX2") (pinfunction "P1_MX2") (pintype "bidirectional"))
      (node (ref "U1") (pin "37") (pinfunction "IO23_37") (pintype "unspecified"))
    )
    (net (code "64") (name "Net-(50-P0)") (class "Default")
      (node (ref "50") (pin "MX1") (pinfunction "P0_MX1") (pintype "bidirectional"))
      (node (ref "D50") (pin "A") (pinfunction "A_A") (pintype "bidirectional"))
    )
    (net (code "65") (name "Net-(51-P0)") (class "Default")
      (node (ref "51") (pin "MX1") (pinfunction "P0_MX1") (pintype "bidirectional"))
      (node (ref "D51") (pin "A") (pinfunction "A_A") (pintype "bidirectional"))
    )
    (net (code "66") (name "Net-(52-P0)") (class "Default")
      (node (ref "52") (pin "MX1") (pinfunction "P0_MX1") (pintype "bidirectional"))
      (node (ref "D52") (pin "A") (pinfunction "A_A") (pintype "bidirectional"))
    )
    (net (code "67") (name "Net-(53-P0)") (class "Default")
      (node (ref "53") (pin "MX1") (pinfunction "P0_MX1") (pintype "bidirectional"))
      (node (ref "D53") (pin "A") (pinfunction "A_A") (pintype "bidirectional"))
    )
    (net (code "68") (name "Net-(54-P0)") (class "Default")
      (node (ref "54") (pin "MX1") (pinfunction "P0_MX1") (pintype "bidirectional"))
      (node (ref "D54") (pin "A") (pinfunction "A_A") (pintype "bidirectional"))
    )
    (net (code "69") (name "Net-(55-P0)") (class "Default")
      (node (ref "55") (pin "MX1") (pinfunction "P0_MX1") (pintype "bidirectional"))
      (node (ref "D55") (pin "A") (pinfunction "A_A") (pintype "bidirectional"))
    )
    (net (code "70") (name "Net-(55-P1)") (class "Default")
      (node (ref "55") (pin "MX2") (pinfunction "P1_MX2") (pintype "bidirectional"))
      (node (ref "56") (pin "MX2") (pinfunction "P1_MX2") (pintype "bidirectional"))
      (node (ref "57") (pin "MX2") (pinfunction "P1_MX2") (pintype "bidirectional"))
      (node (ref "58") (pin "MX2") (pinfunction "P1_MX2") (pintype "bidirectional"))
      (node (ref "59") (pin "MX2") (pinfunction "P1_MX2") (pintype "bidirectional"))
      (node (ref "60") (pin "MX2") (pinfunction "P1_MX2") (pintype "bidirectional"))
      (node (ref "U1") (pin "23") (pinfunction "IO15_23") (pintype "unspecified"))
    )
    (net (code "71") (name "Net-(56-P0)") (class "Default")
      (node (ref "56") (pin "MX1") (pinfunction "P0_MX1") (pintype "bidirectional"))
      (node (ref "D56") (pin "A") (pinfunction "A_A") (pintype "bidirectional"))
    )
    (net (code "72") (name "Net-(57-P0)") (class "Default")
      (node (ref "57") (pin "MX1") (pinfunction "P0_MX1") (pintype "bidirectional"))
      (node (ref "D57") (pin "A") (pinfunction "A_A") (pintype "bidirectional"))
    )
    (net (code "73") (name "Net-(58-P0)") (class "Default")
      (node (ref "58") (pin "MX1") (pinfunction "P0_MX1") (pintype "bidirectional"))
      (node (ref "D58") (pin "A") (pinfunction "A_A") (pintype "bidirectional"))
    )
    (net (code "74") (name "Net-(59-P0)") (class "Default")
      (node (ref "59") (pin "MX1") (pinfunction "P0_MX1") (pintype "bidirectional"))
      (node (ref "D59") (pin "A") (pinfunction "A_A") (pintype "bidirectional"))
    )
    (net (code "75") (name "Net-(60-P0)") (class "Default")
      (node (ref "60") (pin "MX1") (pinfunction "P0_MX1") (pintype "bidirectional"))
      (node (ref "D60") (pin "A") (pinfunction "A_A") (pintype "bidirectional"))
    )
    (net (code "76") (name "Net-(61-P0)") (class "Default")
      (node (ref "61") (pin "MX1") (pinfunction "P0_MX1") (pintype "bidirectional"))
      (node (ref "D61") (pin "A") (pinfunction "A_A") (pintype "bidirectional"))
    )
    (net (code "77") (name "Net-(61-P1)") (class "Default")
      (node (ref "61") (pin "MX2") (pinfunction "P1_MX2") (pintype "bidirectional"))
      (node (ref "62") (pin "MX2") (pinfunction "P1_MX2") (pintype "bidirectional"))
      (node (ref "63") (pin "MX2") (pinfunction "P1_MX2") (pintype "bidirectional"))
      (node (ref "64") (pin "MX2") (pinfunction "P1_MX2") (pintype "bidirectional"))
      (node (ref "65") (pin "MX2") (pinfunction "P1_MX2") (pintype "bidirectional"))
      (node (ref "66") (pin "MX2") (pinfunction "P1_MX2") (pintype "bidirectional"))
      (node (ref "U1") (pin "6") (pinfunction "IO34_6") (pintype "unspecified"))
    )
    (net (code "78") (name "Net-(62-P0)") (class "Default")
      (node (ref "62") (pin "MX1") (pinfunction "P0_MX1") (pintype "bidirectional"))
      (node (ref "D62") (pin "A") (pinfunction "A_A") (pintype "bidirectional"))
    )
    (net (code "79") (name "Net-(63-P0)") (class "Default")
      (node (ref "63") (pin "MX1") (pinfunction "P0_MX1") (pintype "bidirectional"))
      (node (ref "D63") (pin "A") (pinfunction "A_A") (pintype "bidirectional"))
    )
    (net (code "80") (name "Net-(64-P0)") (class "Default")
      (node (ref "64") (pin "MX1") (pinfunction "P0_MX1") (pintype "bidirectional"))
      (node (ref "D64") (pin "A") (pinfunction "A_A") (pintype "bidirectional"))
    )
    (net (code "81") (name "Net-(65-P0)") (class "Default")
      (node (ref "65") (pin "MX1") (pinfunction "P0_MX1") (pintype "bidirectional"))
      (node (ref "D65") (pin "A") (pinfunction "A_A") (pintype "bidirectional"))
    )
    (net (code "82") (name "Net-(66-P0)") (class "Default")
      (node (ref "66") (pin "MX1") (pinfunction "P0_MX1") (pintype "bidirectional"))
      (node (ref "D66") (pin "A") (pinfunction "A_A") (pintype "bidirectional"))
    )
    (net (code "83") (name "Net-(GREEN-A)") (class "Default")
      (node (ref "GREEN") (pin "1") (pinfunction "A_1") (pintype "unspecified"))
      (node (ref "R6") (pin "2") (pinfunction "2_2") (pintype "input"))
    )
    (net (code "84") (name "Net-(LED1-A)") (class "Default")
      (node (ref "LED1") (pin "1") (pinfunction "A_1") (pintype "unspecified"))
      (node (ref "R1") (pin "2") (pinfunction "2_2") (pintype "unspecified"))
    )
    (net (code "85") (name "Net-(LED1-K)") (class "Default")
      (node (ref "C1") (pin "2") (pinfunction "2_2") (pintype "input"))
      (node (ref "C2") (pin "2") (pinfunction "2_2") (pintype "input"))
      (node (ref "LED1") (pin "2") (pinfunction "K_2") (pintype "unspecified"))
      (node (ref "U1") (pin "1") (pinfunction "GND_1") (pintype "unspecified"))
      (node (ref "U2") (pin "1") (pinfunction "GND/ADJ_1") (pintype "unspecified"))
    )
    (net (code "86") (name "Net-(Q1-G1)") (class "Default")
      (node (ref "Q1") (pin "6") (pinfunction "G1_6") (pintype "unspecified"))
      (node (ref "U3") (pin "3") (pinfunction "OC_3") (pintype "unspecified"))
    )
    (net (code "87") (name "Net-(Q1-G2)") (class "Default")
      (node (ref "Q1") (pin "4") (pinfunction "G2_4") (pintype "unspecified"))
      (node (ref "U3") (pin "1") (pinfunction "OD_1") (pintype "unspecified"))
    )
    (net (code "88") (name "Net-(Q2-B)") (class "Default")
      (node (ref "Q2") (pin "2") (pinfunction "B_2") (pintype "unspecified"))
      (node (ref "R7") (pin "2") (pinfunction "2_2") (pintype "unspecified"))
    )
    (net (code "89") (name "Net-(Q2-E)") (class "Default")
      (node (ref "Q2") (pin "1") (pinfunction "E_1") (pintype "unspecified"))
      (node (ref "R2") (pin "1") (pinfunction "1_1") (pintype "unspecified"))
      (node (ref "U5") (pin "19") (pinfunction "RTS_19") (pintype "unspecified"))
    )
    (net (code "90") (name "Net-(Q3-B)") (class "Default")
      (node (ref "Q3") (pin "2") (pinfunction "B_2") (pintype "unspecified"))
      (node (ref "R2") (pin "2") (pinfunction "2_2") (pintype "unspecified"))
    )
    (net (code "91") (name "Net-(Q3-E)") (class "Default")
      (node (ref "Q3") (pin "1") (pinfunction "E_1") (pintype "unspecified"))
      (node (ref "R7") (pin "1") (pinfunction "1_1") (pintype "unspecified"))
      (node (ref "U5") (pin "23") (pinfunction "DTR_23") (pintype "unspecified"))
    )
    (net (code "92") (name "Net-(RED-A)") (class "Default")
      (node (ref "R5") (pin "2") (pinfunction "2_2") (pintype "input"))
      (node (ref "RED") (pin "1") (pinfunction "A_1") (pintype "unspecified"))
    )
    (net (code "93") (name "Net-(U1-IO25)") (class "Default")
      (node (ref "D14") (pin "C") (pinfunction "C_C") (pintype "bidirectional"))
      (node (ref "D20") (pin "C") (pinfunction "C_C") (pintype "bidirectional"))
      (node (ref "D26") (pin "C") (pinfunction "C_C") (pintype "bidirectional"))
      (node (ref "D3") (pin "C") (pinfunction "C_C") (pintype "bidirectional"))
      (node (ref "D32") (pin "C") (pinfunction "C_C") (pintype "bidirectional"))
      (node (ref "D39") (pin "C") (pinfunction "C_C") (pintype "bidirectional"))
      (node (ref "D45") (pin "C") (pinfunction "C_C") (pintype "bidirectional"))
      (node (ref "D51") (pin "C") (pinfunction "C_C") (pintype "bidirectional"))
      (node (ref "D57") (pin "C") (pinfunction "C_C") (pintype "bidirectional"))
      (node (ref "D64") (pin "C") (pinfunction "C_C") (pintype "bidirectional"))
      (node (ref "D8") (pin "C") (pinfunction "C_C") (pintype "bidirectional"))
      (node (ref "U1") (pin "10") (pinfunction "IO25_10") (pintype "unspecified"))
    )
    (net (code "94") (name "Net-(U1-IO26)") (class "Default")
      (node (ref "D13") (pin "C") (pinfunction "C_C") (pintype "bidirectional"))
      (node (ref "D19") (pin "C") (pinfunction "C_C") (pintype "bidirectional"))
      (node (ref "D25") (pin "C") (pinfunction "C_C") (pintype "bidirectional"))
      (node (ref "D31") (pin "C") (pinfunction "C_C") (pintype "bidirectional"))
      (node (ref "D38") (pin "C") (pinfunction "C_C") (pintype "bidirectional"))
      (node (ref "D4") (pin "C") (pinfunction "C_C") (pintype "bidirectional"))
      (node (ref "D44") (pin "C") (pinfunction "C_C") (pintype "bidirectional"))
      (node (ref "D50") (pin "C") (pinfunction "C_C") (pintype "bidirectional"))
      (node (ref "D56") (pin "C") (pinfunction "C_C") (pintype "bidirectional"))
      (node (ref "D65") (pin "C") (pinfunction "C_C") (pintype "bidirectional"))
      (node (ref "D7") (pin "C") (pinfunction "C_C") (pintype "bidirectional"))
      (node (ref "U1") (pin "11") (pinfunction "IO26_11") (pintype "unspecified"))
    )
    (net (code "95") (name "Net-(U1-IO27)") (class "Default")
      (node (ref "D12") (pin "C") (pinfunction "C_C") (pintype "bidirectional"))
      (node (ref "D18") (pin "C") (pinfunction "C_C") (pintype "bidirectional"))
      (node (ref "D24") (pin "C") (pinfunction "C_C") (pintype "bidirectional"))
      (node (ref "D30") (pin "C") (pinfunction "C_C") (pintype "bidirectional"))
      (node (ref "D37") (pin "C") (pinfunction "C_C") (pintype "bidirectional"))
      (node (ref "D43") (pin "C") (pinfunction "C_C") (pintype "bidirectional"))
      (node (ref "D49") (pin "C") (pinfunction "C_C") (pintype "bidirectional"))
      (node (ref "D5") (pin "C") (pinfunction "C_C") (pintype "bidirectional"))
      (node (ref "D55") (pin "C") (pinfunction "C_C") (pintype "bidirectional"))
      (node (ref "D6") (pin "C") (pinfunction "C_C") (pintype "bidirectional"))
      (node (ref "D66") (pin "C") (pinfunction "C_C") (pintype "bidirectional"))
      (node (ref "U1") (pin "12") (pinfunction "IO27_12") (pintype "unspecified"))
    )
    (net (code "96") (name "Net-(U1-IO32)") (class "Default")
      (node (ref "D1") (pin "C") (pinfunction "C_C") (pintype "bidirectional"))
      (node (ref "D10") (pin "C") (pinfunction "C_C") (pintype "bidirectional"))
      (node (ref "D16") (pin "C") (pinfunction "C_C") (pintype "bidirectional"))
      (node (ref "D22") (pin "C") (pinfunction "C_C") (pintype "bidirectional"))
      (node (ref "D28") (pin "C") (pinfunction "C_C") (pintype "bidirectional"))
      (node (ref "D34") (pin "C") (pinfunction "C_C") (pintype "bidirectional"))
      (node (ref "D41") (pin "C") (pinfunction "C_C") (pintype "bidirectional"))
      (node (ref "D47") (pin "C") (pinfunction "C_C") (pintype "bidirectional"))
      (node (ref "D53") (pin "C") (pinfunction "C_C") (pintype "bidirectional"))
      (node (ref "D59") (pin "C") (pinfunction "C_C") (pintype "bidirectional"))
      (node (ref "D62") (pin "C") (pinfunction "C_C") (pintype "bidirectional"))
      (node (ref "U1") (pin "8") (pinfunction "IO32_8") (pintype "unspecified"))
    )
    (net (code "97") (name "Net-(U1-IO33)") (class "Default")
      (node (ref "D15") (pin "C") (pinfunction "C_C") (pintype "bidirectional"))
      (node (ref "D2") (pin "C") (pinfunction "C_C") (pintype "bidirectional"))
      (node (ref "D21") (pin "C") (pinfunction "C_C") (pintype "bidirectional"))
      (node (ref "D27") (pin "C") (pinfunction "C_C") (pintype "bidirectional"))
      (node (ref "D33") (pin "C") (pinfunction "C_C") (pintype "bidirectional"))
      (node (ref "D40") (pin "C") (pinfunction "C_C") (pintype "bidirectional"))
      (node (ref "D46") (pin "C") (pinfunction "C_C") (pintype "bidirectional"))
      (node (ref "D52") (pin "C") (pinfunction "C_C") (pintype "bidirectional"))
      (node (ref "D58") (pin "C") (pinfunction "C_C") (pintype "bidirectional"))
      (node (ref "D63") (pin "C") (pinfunction "C_C") (pintype "bidirectional"))
      (node (ref "D9") (pin "C") (pinfunction "C_C") (pintype "bidirectional"))
      (node (ref "U1") (pin "9") (pinfunction "IO33_9") (pintype "unspecified"))
    )
    (net (code "98") (name "Net-(U1-IO35)") (class "Default")
      (node (ref "D11") (pin "C") (pinfunction "C_C") (pintype "bidirectional"))
      (node (ref "D17") (pin "C") (pinfunction "C_C") (pintype "bidirectional"))
      (node (ref "D23") (pin "C") (pinfunction "C_C") (pintype "bidirectional"))
      (node (ref "D29") (pin "C") (pinfunction "C_C") (pintype "bidirectional"))
      (node (ref "D35") (pin "C") (pinfunction "C_C") (pintype "bidirectional"))
      (node (ref "D36") (pin "C") (pinfunction "C_C") (pintype "bidirectional"))
      (node (ref "D42") (pin "C") (pinfunction "C_C") (pintype "bidirectional"))
      (node (ref "D48") (pin "C") (pinfunction "C_C") (pintype "bidirectional"))
      (node (ref "D54") (pin "C") (pinfunction "C_C") (pintype "bidirectional"))
      (node (ref "D60") (pin "C") (pinfunction "C_C") (pintype "bidirectional"))
      (node (ref "D61") (pin "C") (pinfunction "C_C") (pintype "bidirectional"))
      (node (ref "U1") (pin "7") (pinfunction "IO35_7") (pintype "unspecified"))
    )
    (net (code "99") (name "Net-(U3-CS)") (class "Default")
      (node (ref "R4") (pin "2") (pinfunction "2_2") (pintype "unspecified"))
      (node (ref "U3") (pin "2") (pinfunction "CS_2") (pintype "unspecified"))
    )
    (net (code "100") (name "Net-(U3-VCC)") (class "Default")
      (node (ref "C4") (pin "1") (pinfunction "1_1") (pintype "input"))
      (node (ref "R9") (pin "1") (pinfunction "1_1") (pintype "input"))
      (node (ref "U3") (pin "5") (pinfunction "VCC_5") (pintype "unspecified"))
    )
    (net (code "101") (name "Net-(U4-PROG)") (class "Default")
      (node (ref "R3") (pin "1") (pinfunction "1_1") (pintype "input"))
      (node (ref "U4") (pin "2") (pinfunction "PROG_2") (pintype "unspecified"))
    )
    (net (code "102") (name "Net-(U5-D+)") (class "Default")
      (node (ref "U5") (pin "3") (pinfunction "D+_3") (pintype "unspecified"))
      (node (ref "USB3") (pin "3") (pinfunction "D+_3") (pintype "unspecified"))
    )
    (net (code "103") (name "Net-(U5-D-)") (class "Default")
      (node (ref "U5") (pin "4") (pinfunction "D-_4") (pintype "unspecified"))
      (node (ref "USB3") (pin "2") (pinfunction "D-_2") (pintype "unspecified"))
    )
    (net (code "104") (name "Net-(U5-VDD)") (class "Default")
      (node (ref "C7") (pin "2") (pinfunction "2_2") (pintype "input"))
      (node (ref "U5") (pin "6") (pinfunction "VDD_6") (pintype "unspecified"))
    )
    (net (code "105") (name "RX") (class "Default")
      (node (ref "FLASH_FTDI") (pin "3") (pinfunction "3_3") (pintype "unspecified"))
      (node (ref "U1") (pin "34") (pinfunction "RXD0_34") (pintype "unspecified"))
      (node (ref "U5") (pin "21") (pinfunction "TXD_21") (pintype "unspecified"))
    )
    (net (code "106") (name "SWB+") (class "Default")
      (node (ref "C1") (pin "1") (pinfunction "1_1") (pintype "input"))
      (node (ref "C5") (pin "2") (pinfunction "2_2") (pintype "unspecified"))
      (node (ref "R9") (pin "2") (pinfunction "2_2") (pintype "input"))
      (node (ref "SWITCH1") (pin "2") (pinfunction "w_2") (pintype "input"))
      (node (ref "U2") (pin "3") (pinfunction "Vin_3") (pintype "unspecified"))
      (node (ref "U4") (pin "5") (pinfunction "BAT_5") (pintype "unspecified"))
    )
    (net (code "107") (name "TX") (class "Default")
      (node (ref "FLASH_FTDI") (pin "2") (pinfunction "2_2") (pintype "unspecified"))
      (node (ref "U1") (pin "35") (pinfunction "TXD0_35") (pintype "unspecified"))
      (node (ref "U5") (pin "20") (pinfunction "RXD_20") (pintype "unspecified"))
    )
    (net (code "108") (name "VCC5") (class "Default")
      (node (ref "C3") (pin "2") (pinfunction "2_2") (pintype "input"))
      (node (ref "U4") (pin "4") (pinfunction "VCC_4") (pintype "unspecified"))
      (node (ref "USB3") (pin "1") (pinfunction "VBUS_1") (pintype "unspecified"))
    )
    (net (code "109") (name "VDD33") (class "Default")
      (node (ref "C2") (pin "1") (pinfunction "1_1") (pintype "input"))
      (node (ref "FLASH_FTDI") (pin "1") (pinfunction "1_1") (pintype "unspecified"))
      (node (ref "PULLUP1") (pin "1") (pinfunction "1_1") (pintype "input"))
      (node (ref "R1") (pin "1") (pinfunction "1_1") (pintype "unspecified"))
      (node (ref "U1") (pin "2") (pinfunction "VDD33_2") (pintype "unspecified"))
      (node (ref "U2") (pin "2") (pinfunction "Vout_2") (pintype "unspecified"))
      (node (ref "U5") (pin "7") (pinfunction "REGIN_7") (pintype "unspecified"))
      (node (ref "U5") (pin "8") (pinfunction "VBUS_8") (pintype "unspecified"))
    )
    (net (code "110") (name "greenled") (class "Default")
      (node (ref "R5") (pin "1") (pinfunction "1_1") (pintype "input"))
      (node (ref "U4") (pin "6") (pinfunction "STDBY_6") (pintype "unspecified"))
    )
    (net (code "111") (name "redled") (class "Default")
      (node (ref "R6") (pin "1") (pinfunction "1_1") (pintype "input"))
      (node (ref "U4") (pin "7") (pinfunction "CHRG_7") (pintype "unspecified"))
    )
    (net (code "112") (name "unconnected-(Q1-D12-Pad2)") (class "Default")
      (node (ref "Q1") (pin "2") (pinfunction "D12_2") (pintype "unspecified+no_connect"))
    )
    (net (code "113") (name "unconnected-(Q1-D12-Pad5)") (class "Default")
      (node (ref "Q1") (pin "5") (pinfunction "D12_5") (pintype "unspecified+no_connect"))
    )
    (net (code "114") (name "unconnected-(U1-CLK-Pad20)") (class "Default")
      (node (ref "U1") (pin "20") (pinfunction "CLK_20") (pintype "unspecified+no_connect"))
    )
    (net (code "115") (name "unconnected-(U1-CMD-Pad19)") (class "Default")
      (node (ref "U1") (pin "19") (pinfunction "CMD_19") (pintype "unspecified+no_connect"))
    )
    (net (code "116") (name "unconnected-(U1-IO12-Pad14)") (class "Default")
      (node (ref "U1") (pin "14") (pinfunction "IO12_14") (pintype "unspecified+no_connect"))
    )
    (net (code "117") (name "unconnected-(U1-IO14-Pad13)") (class "Default")
      (node (ref "U1") (pin "13") (pinfunction "IO14_13") (pintype "unspecified+no_connect"))
    )
    (net (code "118") (name "unconnected-(U1-NC-Pad27)") (class "Default")
      (node (ref "U1") (pin "27") (pinfunction "NC_27") (pintype "unspecified+no_connect"))
    )
    (net (code "119") (name "unconnected-(U1-NC-Pad28)") (class "Default")
      (node (ref "U1") (pin "28") (pinfunction "NC_28") (pintype "unspecified+no_connect"))
    )
    (net (code "120") (name "unconnected-(U1-NC-Pad32)") (class "Default")
      (node (ref "U1") (pin "32") (pinfunction "NC_32") (pintype "unspecified+no_connect"))
    )
    (net (code "121") (name "unconnected-(U1-SD0-Pad21)") (class "Default")
      (node (ref "U1") (pin "21") (pinfunction "SD0_21") (pintype "unspecified+no_connect"))
    )
    (net (code "122") (name "unconnected-(U1-SD1-Pad22)") (class "Default")
      (node (ref "U1") (pin "22") (pinfunction "SD1_22") (pintype "unspecified+no_connect"))
    )
    (net (code "123") (name "unconnected-(U1-SD2-Pad17)") (class "Default")
      (node (ref "U1") (pin "17") (pinfunction "SD2_17") (pintype "unspecified+no_connect"))
    )
    (net (code "124") (name "unconnected-(U1-SD3-Pad18)") (class "Default")
      (node (ref "U1") (pin "18") (pinfunction "SD3_18") (pintype "unspecified+no_connect"))
    )
    (net (code "125") (name "unconnected-(U1-SENSOR_VN-Pad5)") (class "Default")
      (node (ref "U1") (pin "5") (pinfunction "SENSOR_VN_5") (pintype "unspecified+no_connect"))
    )
    (net (code "126") (name "unconnected-(U1-SENSOR_VP-Pad4)") (class "Default")
      (node (ref "U1") (pin "4") (pinfunction "SENSOR_VP_4") (pintype "unspecified+no_connect"))
    )
    (net (code "127") (name "unconnected-(U2-Vout-Pad4)") (class "Default")
      (node (ref "U2") (pin "4") (pinfunction "Vout_4") (pintype "unspecified+no_connect"))
    )
    (net (code "128") (name "unconnected-(U3-TD-Pad4)") (class "Default")
      (node (ref "U3") (pin "4") (pinfunction "TD_4") (pintype "unspecified+no_connect"))
    )
    (net (code "129") (name "unconnected-(U4-CE-Pad8)") (class "Default")
      (node (ref "U4") (pin "8") (pinfunction "CE_8") (pintype "unspecified+no_connect"))
    )
    (net (code "130") (name "unconnected-(U5-CTS-Pad18)") (class "Default")
      (node (ref "U5") (pin "18") (pinfunction "CTS_18") (pintype "unspecified+no_connect"))
    )
    (net (code "131") (name "unconnected-(U5-DCD-Pad24)") (class "Default")
      (node (ref "U5") (pin "24") (pinfunction "DCD_24") (pintype "unspecified+no_connect"))
    )
    (net (code "132") (name "unconnected-(U5-DSR-Pad22)") (class "Default")
      (node (ref "U5") (pin "22") (pinfunction "DSR_22") (pintype "unspecified+no_connect"))
    )
    (net (code "133") (name "unconnected-(U5-GPIO.1-Pad13)") (class "Default")
      (node (ref "U5") (pin "13") (pinfunction "GPIO.1_13") (pintype "unspecified+no_connect"))
    )
    (net (code "134") (name "unconnected-(U5-GPIO.2-Pad12)") (class "Default")
      (node (ref "U5") (pin "12") (pinfunction "GPIO.2_12") (pintype "unspecified+no_connect"))
    )
    (net (code "135") (name "unconnected-(U5-GPIO.3-Pad11)") (class "Default")
      (node (ref "U5") (pin "11") (pinfunction "GPIO.3_11") (pintype "unspecified+no_connect"))
    )
    (net (code "136") (name "unconnected-(U5-NC-Pad10)") (class "Default")
      (node (ref "U5") (pin "10") (pinfunction "NC_10") (pintype "unspecified+no_connect"))
    )
    (net (code "137") (name "unconnected-(U5-RI-Pad1)") (class "Default")
      (node (ref "U5") (pin "1") (pinfunction "RI_1") (pintype "unspecified+no_connect"))
    )
    (net (code "138") (name "unconnected-(U5-RST#-Pad9)") (class "Default")
      (node (ref "U5") (pin "9") (pinfunction "RST#_9") (pintype "unspecified+no_connect"))
    )
    (net (code "139") (name "unconnected-(U5-SUSPEND#-Pad15)") (class "Default")
      (node (ref "U5") (pin "15") (pinfunction "SUSPEND#_15") (pintype "unspecified+no_connect"))
    )
    (net (code "140") (name "unconnected-(U5-SUSPEND-Pad17)") (class "Default")
      (node (ref "U5") (pin "17") (pinfunction "SUSPEND_17") (pintype "unspecified+no_connect"))
    )
    (net (code "141") (name "unconnected-(U5-VIO-Pad5)") (class "Default")
      (node (ref "U5") (pin "5") (pinfunction "VIO_5") (pintype "unspecified+no_connect"))
    )
    (net (code "142") (name "unconnected-(U5-VPP-Pad16)") (class "Default")
      (node (ref "U5") (pin "16") (pinfunction "VPP_16") (pintype "unspecified+no_connect"))
    )
    (net (code "143") (name "unconnected-(USB3-ID-Pad4)") (class "Default")
      (node (ref "USB3") (pin "4") (pinfunction "ID_4") (pintype "unspecified+no_connect"))
    )
  )
)
